# ESP32-esp32-c3-mini-module.net
KiCad netlist of a schematic drawn in Altium Designer
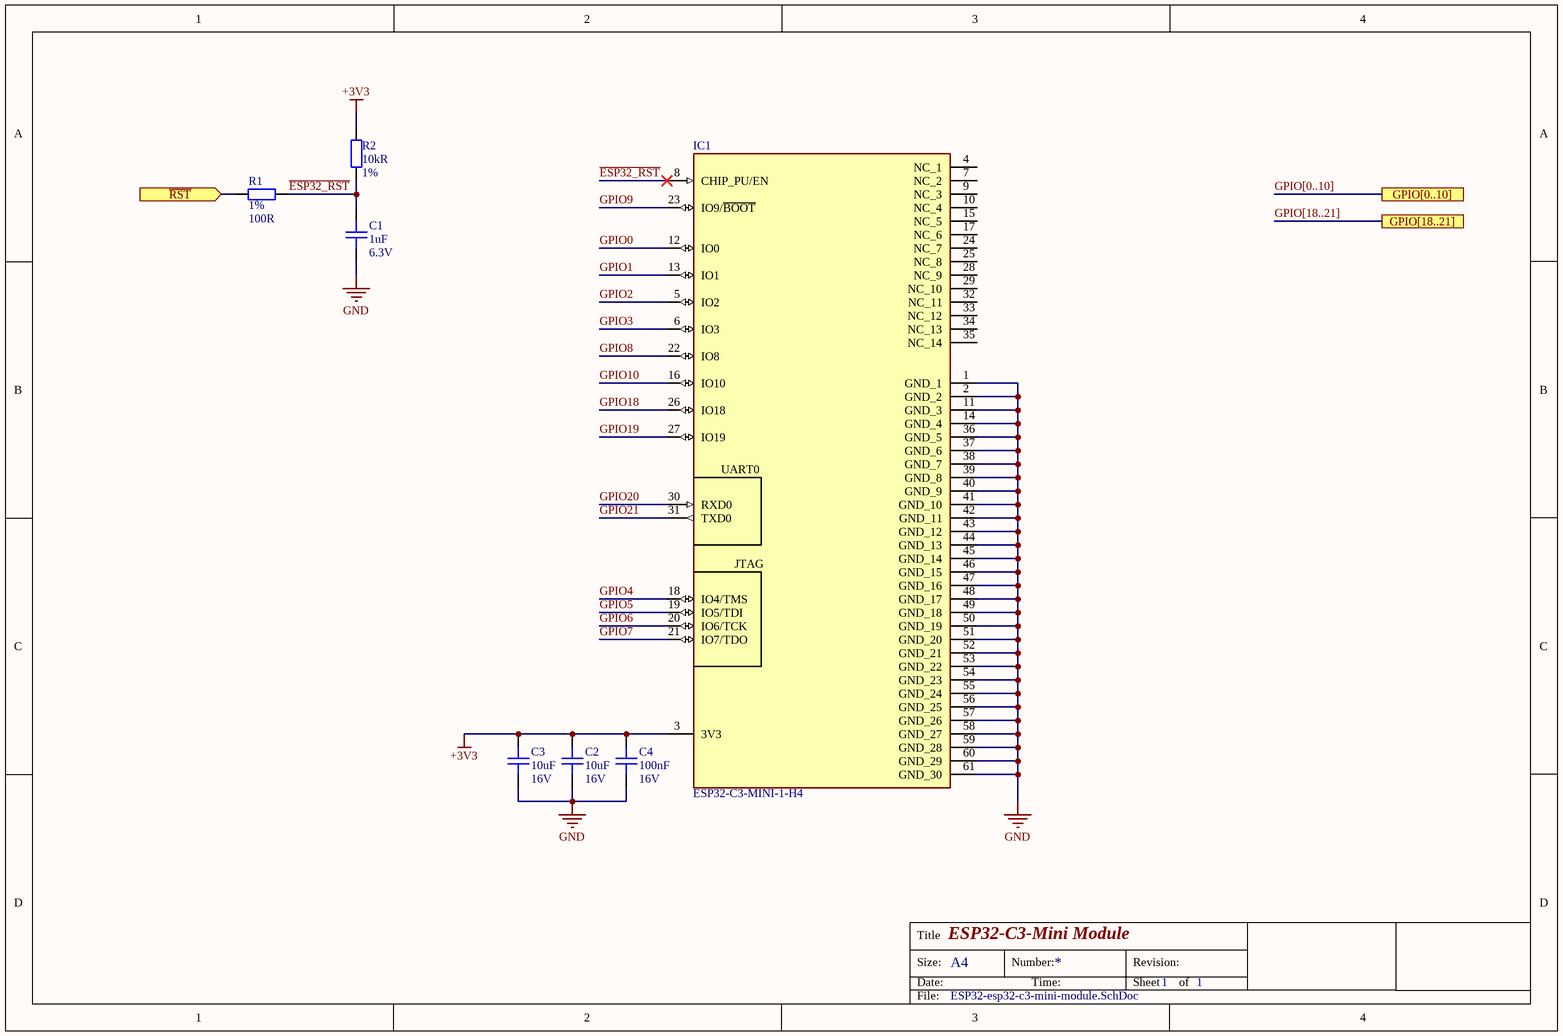
[diagram p0: ESP32-esp32-c3-mini-module.SchDoc]

(export (version "E")
  (design (tool "Eeschema 10.0.6"))
  (components
    (comp (ref "C1")
      (value "CAP CER 1UF 6.3V X5R 0402")
      (footprint "C0402")
      (description "1µF ±10% 6.3V Ceramic Capacitor X5R 0402 (1005 Metric)")
      (fields
        (field (name "MANUFACTURER") "Yageo")
        (field (name "MANUFACTURER PART NUMBER") "CC0402KRX5R5BB105")
        (field (name "CAPACITANCE") "1uF")
        (field (name "VOLTAGE RATING") "6.3V")
      )
      (libsource (lib "Control_Board_Model_C201") (part "CAP CER 1UF 6.3V X5R 0402"))
    )
    (comp (ref "C2")
      (value "CAP CER 10UF 16V X5R 0603")
      (footprint "C0603")
      (description "10µF ±10% 16V Ceramic Capacitor X5R 0603 (1608 Metric)")
      (fields
        (field (name "MANUFACTURER") "Murata")
        (field (name "MANUFACTURER PART NUMBER") "GRM188R61C106KAALJ")
        (field (name "CAPACITANCE") "10uF")
        (field (name "VOLTAGE RATING") "16V")
      )
      (libsource (lib "capacitors_smd") (part "CAP CER 10UF 16V X5R 0603"))
    )
    (comp (ref "C3")
      (value "CAP CER 10UF 16V X5R 0603")
      (footprint "C0603")
      (description "10µF ±10% 16V Ceramic Capacitor X5R 0603 (1608 Metric)")
      (fields
        (field (name "MANUFACTURER") "Murata")
        (field (name "MANUFACTURER PART NUMBER") "GRM188R61C106KAALJ")
        (field (name "CAPACITANCE") "10uF")
        (field (name "VOLTAGE RATING") "16V")
      )
      (libsource (lib "capacitors_smd") (part "CAP CER 10UF 16V X5R 0603"))
    )
    (comp (ref "C4")
      (value "CAP CER 0.1UF 16V X7R 0402")
      (footprint "C0402")
      (description "0.1µF ±10% 16V Ceramic Capacitor X7R 0402 (1005 Metric)")
      (fields
        (field (name "MANUFACTURER PART NUMBER") "CC0402KRX7R7BB104")
        (field (name "MANUFACTURER") "Yageo")
        (field (name "CAPACITANCE") "100nF")
        (field (name "VOLTAGE") "16V")
      )
      (libsource (lib "capacitors_smd") (part "CAP CER 0.1UF 16V X7R 0402"))
    )
    (comp (ref "IC1")
      (value "ESP32-C3-MINI-1-H4")
      (footprint "ESP32C3MINI1H4")
      (description "Integrated Circuit")
      (libsource (lib "ESP-32-C3-MINI-v1.0") (part "ESP32-C3-MINI-1-H4"))
    )
    (comp (ref "R1")
      (value "RES SMD 100 OHM 1% 1/16W 0402")
      (footprint "R0402")
      (description "100 Ohms ±1% 0.063W, 1/16W Chip Resistor 0402 (1005 Metric) Moisture Resistant Thick Film")
      (fields
        (field (name "MANUFACTURER PART NUMBER") "RC0402FR-07100RL")
        (field (name "MANUFACTURER") "Yageo")
        (field (name "TOLERANCE") "1%")
        (field (name "RESISTANCE") "100R")
      )
      (libsource (lib "resistors_smd") (part "RES SMD 100 OHM 1% 1/16W 0402"))
    )
    (comp (ref "R2")
      (value "RES SMD 10K OHM 1% 1/16W 0402")
      (footprint "R0402")
      (description "10 kOhms ±1% 0.063W, 1/16W Chip Resistor 0402 (1005 Metric) Moisture Resistant Thick Film")
      (fields
        (field (name "MANUFACTURER PART NUMBER") "RC0402FR-0710KP")
        (field (name "MANUFACTURER") "Yageo")
        (field (name "RESISTANCE") "10kR")
        (field (name "TOLERANCE") "1%")
      )
      (libsource (lib "resistors_smd") (part "RES SMD 10K OHM 1% 1/16W 0402"))
    )
  )
  (nets
    (net (code "1") (name "+3V3") (class "Default")
      (node (ref "C2") (pin "2") (pinfunction "2_2") (pintype "passive"))
      (node (ref "C3") (pin "2") (pinfunction "2_2") (pintype "passive"))
      (node (ref "C4") (pin "2") (pinfunction "2_2") (pintype "passive"))
      (node (ref "IC1") (pin "3") (pinfunction "3V3_3") (pintype "power_in"))
      (node (ref "R2") (pin "1") (pinfunction "1_1") (pintype "passive"))
    )
    (net (code "2") (name "/ESP32_RST") (class "Default")
      (node (ref "C1") (pin "2") (pinfunction "2_2") (pintype "passive"))
      (node (ref "IC1") (pin "8") (pinfunction "CHIP_PU/EN_8") (pintype "input"))
      (node (ref "R1") (pin "1") (pinfunction "1_1") (pintype "passive"))
      (node (ref "R2") (pin "2") (pinfunction "2_2") (pintype "passive"))
    )
    (net (code "3") (name "/GPIO0") (class "Default")
      (node (ref "IC1") (pin "12") (pinfunction "IO0_12") (pintype "bidirectional"))
    )
    (net (code "4") (name "/GPIO1") (class "Default")
      (node (ref "IC1") (pin "13") (pinfunction "IO1_13") (pintype "bidirectional"))
    )
    (net (code "5") (name "/GPIO2") (class "Default")
      (node (ref "IC1") (pin "5") (pinfunction "IO2_5") (pintype "bidirectional"))
    )
    (net (code "6") (name "/GPIO3") (class "Default")
      (node (ref "IC1") (pin "6") (pinfunction "IO3_6") (pintype "bidirectional"))
    )
    (net (code "7") (name "/GPIO4") (class "Default")
      (node (ref "IC1") (pin "18") (pinfunction "IO4/TMS_18") (pintype "bidirectional"))
    )
    (net (code "8") (name "/GPIO5") (class "Default")
      (node (ref "IC1") (pin "19") (pinfunction "IO5/TDI_19") (pintype "bidirectional"))
    )
    (net (code "9") (name "/GPIO6") (class "Default")
      (node (ref "IC1") (pin "20") (pinfunction "IO6/TCK_20") (pintype "bidirectional"))
    )
    (net (code "10") (name "/GPIO7") (class "Default")
      (node (ref "IC1") (pin "21") (pinfunction "IO7/TDO_21") (pintype "bidirectional"))
    )
    (net (code "11") (name "/GPIO8") (class "Default")
      (node (ref "IC1") (pin "22") (pinfunction "IO8_22") (pintype "bidirectional"))
    )
    (net (code "12") (name "/GPIO9") (class "Default")
      (node (ref "IC1") (pin "23") (pinfunction "IO9/~{BOOT}_23") (pintype "bidirectional"))
    )
    (net (code "13") (name "/GPIO10") (class "Default")
      (node (ref "IC1") (pin "16") (pinfunction "IO10_16") (pintype "bidirectional"))
    )
    (net (code "14") (name "/GPIO18") (class "Default")
      (node (ref "IC1") (pin "26") (pinfunction "IO18_26") (pintype "bidirectional"))
    )
    (net (code "15") (name "/GPIO19") (class "Default")
      (node (ref "IC1") (pin "27") (pinfunction "IO19_27") (pintype "bidirectional"))
    )
    (net (code "16") (name "/GPIO20") (class "Default")
      (node (ref "IC1") (pin "30") (pinfunction "RXD0_30") (pintype "input"))
    )
    (net (code "17") (name "/GPIO21") (class "Default")
      (node (ref "IC1") (pin "31") (pinfunction "TXD0_31") (pintype "output"))
    )
    (net (code "20") (name "/RST") (class "Default")
      (node (ref "R1") (pin "2") (pinfunction "2_2") (pintype "passive"))
    )
    (net (code "21") (name "GND") (class "Default")
      (node (ref "C1") (pin "1") (pinfunction "1_1") (pintype "passive"))
      (node (ref "C2") (pin "1") (pinfunction "1_1") (pintype "passive"))
      (node (ref "C3") (pin "1") (pinfunction "1_1") (pintype "passive"))
      (node (ref "C4") (pin "1") (pinfunction "1_1") (pintype "passive"))
      (node (ref "IC1") (pin "1") (pinfunction "GND_1_1") (pintype "power_in"))
      (node (ref "IC1") (pin "11") (pinfunction "GND_3_11") (pintype "power_in"))
      (node (ref "IC1") (pin "14") (pinfunction "GND_4_14") (pintype "power_in"))
      (node (ref "IC1") (pin "2") (pinfunction "GND_2_2") (pintype "power_in"))
      (node (ref "IC1") (pin "36") (pinfunction "GND_5_36") (pintype "power_in"))
      (node (ref "IC1") (pin "37") (pinfunction "GND_6_37") (pintype "power_in"))
      (node (ref "IC1") (pin "38") (pinfunction "GND_7_38") (pintype "power_in"))
      (node (ref "IC1") (pin "39") (pinfunction "GND_8_39") (pintype "power_in"))
      (node (ref "IC1") (pin "40") (pinfunction "GND_9_40") (pintype "power_in"))
      (node (ref "IC1") (pin "41") (pinfunction "GND_10_41") (pintype "power_in"))
      (node (ref "IC1") (pin "42") (pinfunction "GND_11_42") (pintype "power_in"))
      (node (ref "IC1") (pin "43") (pinfunction "GND_12_43") (pintype "power_in"))
      (node (ref "IC1") (pin "44") (pinfunction "GND_13_44") (pintype "power_in"))
      (node (ref "IC1") (pin "45") (pinfunction "GND_14_45") (pintype "power_in"))
      (node (ref "IC1") (pin "46") (pinfunction "GND_15_46") (pintype "power_in"))
      (node (ref "IC1") (pin "47") (pinfunction "GND_16_47") (pintype "power_in"))
      (node (ref "IC1") (pin "48") (pinfunction "GND_17_48") (pintype "power_in"))
      (node (ref "IC1") (pin "49") (pinfunction "GND_18_49") (pintype "power_in"))
      (node (ref "IC1") (pin "50") (pinfunction "GND_19_50") (pintype "power_in"))
      (node (ref "IC1") (pin "51") (pinfunction "GND_20_51") (pintype "power_in"))
      (node (ref "IC1") (pin "52") (pinfunction "GND_21_52") (pintype "power_in"))
      (node (ref "IC1") (pin "53") (pinfunction "GND_22_53") (pintype "power_in"))
      (node (ref "IC1") (pin "54") (pinfunction "GND_23_54") (pintype "power_in"))
      (node (ref "IC1") (pin "55") (pinfunction "GND_24_55") (pintype "power_in"))
      (node (ref "IC1") (pin "56") (pinfunction "GND_25_56") (pintype "power_in"))
      (node (ref "IC1") (pin "57") (pinfunction "GND_26_57") (pintype "power_in"))
      (node (ref "IC1") (pin "58") (pinfunction "GND_27_58") (pintype "power_in"))
      (node (ref "IC1") (pin "59") (pinfunction "GND_28_59") (pintype "power_in"))
      (node (ref "IC1") (pin "60") (pinfunction "GND_29_60") (pintype "power_in"))
      (node (ref "IC1") (pin "61") (pinfunction "GND_30_61") (pintype "power_in"))
    )
    (net (code "22") (name "unconnected-(IC1-NC_1-Pad4)") (class "Default")
      (node (ref "IC1") (pin "4") (pinfunction "NC_1_4") (pintype "tri_state"))
    )
    (net (code "23") (name "unconnected-(IC1-NC_2-Pad7)") (class "Default")
      (node (ref "IC1") (pin "7") (pinfunction "NC_2_7") (pintype "tri_state"))
    )
    (net (code "24") (name "unconnected-(IC1-NC_3-Pad9)") (class "Default")
      (node (ref "IC1") (pin "9") (pinfunction "NC_3_9") (pintype "tri_state"))
    )
    (net (code "25") (name "unconnected-(IC1-NC_4-Pad10)") (class "Default")
      (node (ref "IC1") (pin "10") (pinfunction "NC_4_10") (pintype "tri_state"))
    )
    (net (code "26") (name "unconnected-(IC1-NC_5-Pad15)") (class "Default")
      (node (ref "IC1") (pin "15") (pinfunction "NC_5_15") (pintype "tri_state"))
    )
    (net (code "27") (name "unconnected-(IC1-NC_6-Pad17)") (class "Default")
      (node (ref "IC1") (pin "17") (pinfunction "NC_6_17") (pintype "tri_state"))
    )
    (net (code "28") (name "unconnected-(IC1-NC_7-Pad24)") (class "Default")
      (node (ref "IC1") (pin "24") (pinfunction "NC_7_24") (pintype "tri_state"))
    )
    (net (code "29") (name "unconnected-(IC1-NC_8-Pad25)") (class "Default")
      (node (ref "IC1") (pin "25") (pinfunction "NC_8_25") (pintype "tri_state"))
    )
    (net (code "30") (name "unconnected-(IC1-NC_9-Pad28)") (class "Default")
      (node (ref "IC1") (pin "28") (pinfunction "NC_9_28") (pintype "tri_state"))
    )
    (net (code "31") (name "unconnected-(IC1-NC_10-Pad29)") (class "Default")
      (node (ref "IC1") (pin "29") (pinfunction "NC_10_29") (pintype "tri_state"))
    )
    (net (code "32") (name "unconnected-(IC1-NC_11-Pad32)") (class "Default")
      (node (ref "IC1") (pin "32") (pinfunction "NC_11_32") (pintype "tri_state"))
    )
    (net (code "33") (name "unconnected-(IC1-NC_12-Pad33)") (class "Default")
      (node (ref "IC1") (pin "33") (pinfunction "NC_12_33") (pintype "tri_state"))
    )
    (net (code "34") (name "unconnected-(IC1-NC_13-Pad34)") (class "Default")
      (node (ref "IC1") (pin "34") (pinfunction "NC_13_34") (pintype "tri_state"))
    )
    (net (code "35") (name "unconnected-(IC1-NC_14-Pad35)") (class "Default")
      (node (ref "IC1") (pin "35") (pinfunction "NC_14_35") (pintype "tri_state"))
    )
  )
)
